# BatteryEmulator.net
KiCad netlist of a schematic drawn in Altium Designer
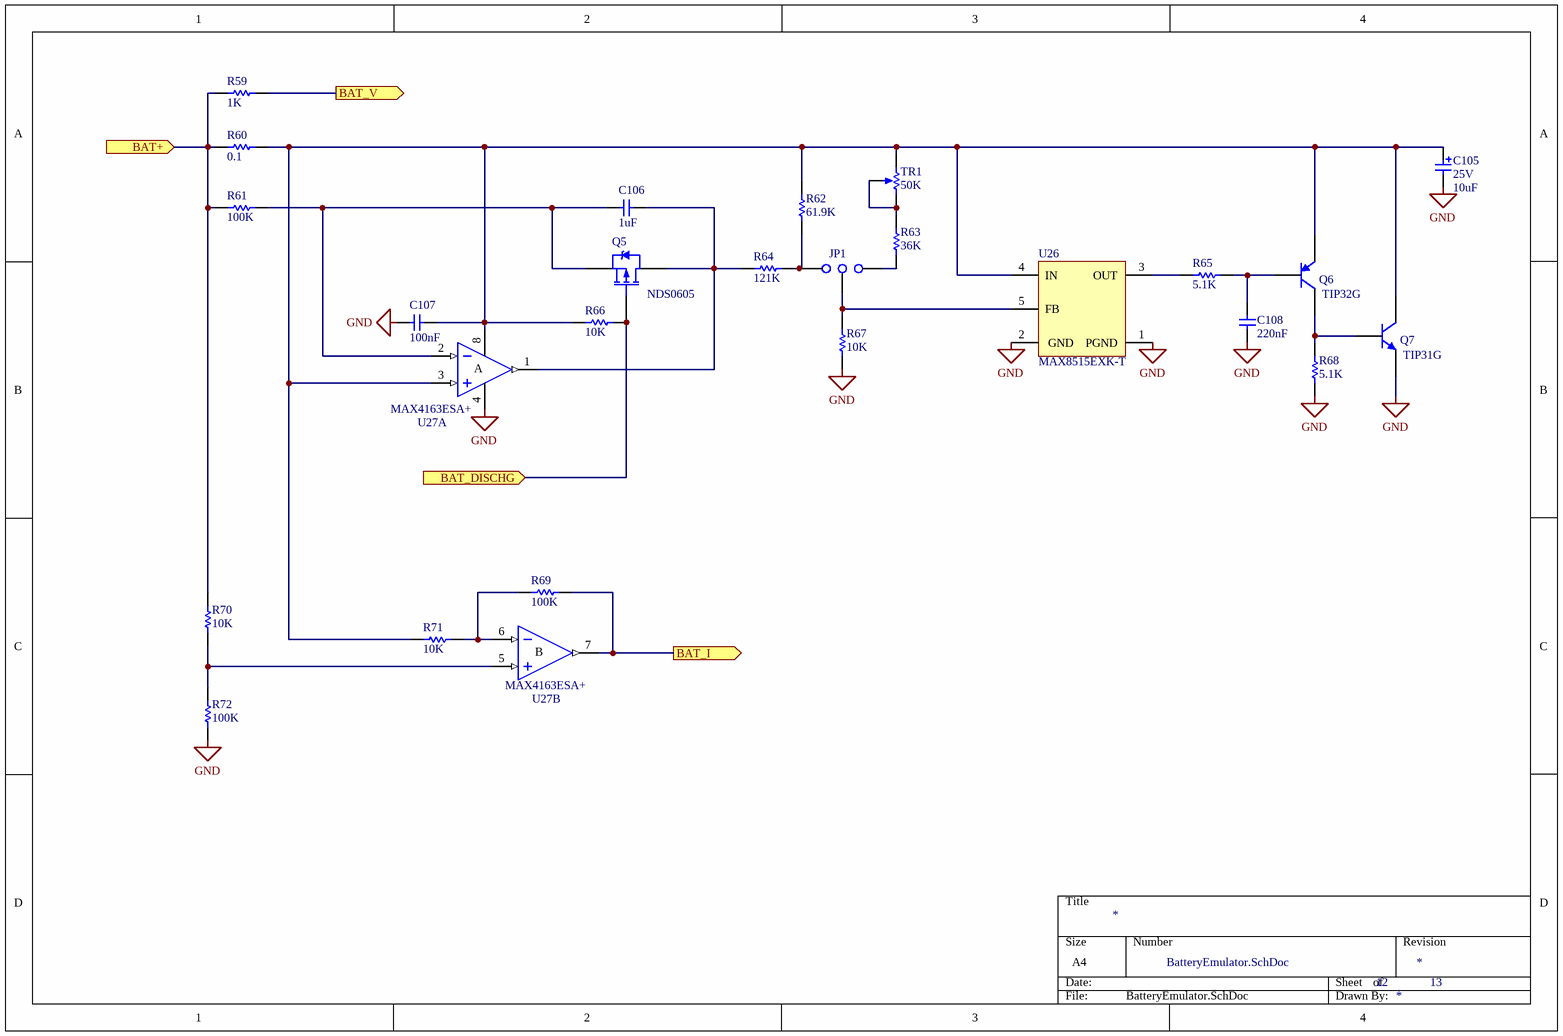
[diagram p0: BatteryEmulator.SchDoc]

(export (version "E")
  (design (tool "Eeschema 10.0.6"))
  (components
    (comp (ref "C105")
      (value "25V")
      (footprint "Cap Elet SMD 6.3 mm CASE D")
      (description "Condensatore elettrolitico")
      (fields (field (name "ALTIUM_VALUE") "10uF"))
      (libsource (lib "Plume") (part "Cap Elettrolitico"))
    )
    (comp (ref "C106")
      (value "1uF")
      (footprint "Cap Polyester 5 mm")
      (description "Polyester Capacitor")
      (fields (field (name "Comment") "Cap Polyester"))
      (libsource (lib "Plume") (part "Cap Polyester"))
    )
    (comp (ref "C107")
      (value "100nF")
      (footprint "0603M-C")
      (description "Ceramic Capacitor")
      (fields (field (name "Comment") "Cap Ceramic"))
      (libsource (lib "Plume") (part "Cap Ceramic"))
    )
    (comp (ref "C108")
      (value "220nF")
      (footprint "0603M-C")
      (description "Ceramic Capacitor")
      (fields (field (name "Comment") "Cap Ceramic"))
      (libsource (lib "Plume") (part "Cap Ceramic"))
    )
    (comp (ref "JP1") (value "Jumper 3 pin") (footprint "HEADER3") (libsource (lib "Plume") (part "Jumper3")))
    (comp (ref "Q5")
      (value "NDS0605")
      (footprint "SOT23 PMV65XP MOS")
      (description "Mosfet canale P Enhancement")
      (libsource (lib "Plume") (part "Transistor PMOS Enhancement"))
    )
    (comp (ref "Q6")
      (value "TIP32G")
      (footprint "TO220_BJT")
      (description "PNP Bipolar Transistor")
      (fields (field (name "PUBLISHER") "Altium Limited"))
      (libsource (lib "Plume") (part "Transistor PNP"))
    )
    (comp (ref "Q7")
      (value "TIP31G")
      (footprint "TO220_BJT")
      (description "NPN Bipolar Transistor")
      (libsource (lib "Plume") (part "Transistor NPN"))
    )
    (comp (ref "R59")
      (value "1K")
      (footprint "0603M")
      (description "Resistor")
      (libsource (lib "Plume") (part "Resistor"))
    )
    (comp (ref "R60")
      (value "0.1")
      (footprint "1206M")
      (description "Resistor")
      (libsource (lib "Plume") (part "Resistor"))
    )
    (comp (ref "R61")
      (value "100K")
      (footprint "0603M")
      (description "Resistor")
      (libsource (lib "Plume") (part "Resistor"))
    )
    (comp (ref "R62")
      (value "61.9K")
      (footprint "0603M")
      (description "Resistor")
      (libsource (lib "Plume") (part "Resistor"))
    )
    (comp (ref "R63")
      (value "36K")
      (footprint "0603M")
      (description "Resistor")
      (libsource (lib "Plume") (part "Resistor"))
    )
    (comp (ref "R64")
      (value "121K")
      (footprint "0603M")
      (description "Resistor")
      (libsource (lib "Plume") (part "Resistor"))
    )
    (comp (ref "R65")
      (value "5.1K")
      (footprint "0603M")
      (description "Resistor")
      (libsource (lib "Plume") (part "Resistor"))
    )
    (comp (ref "R66")
      (value "10K")
      (footprint "0603M")
      (description "Resistor")
      (libsource (lib "Plume") (part "Resistor"))
    )
    (comp (ref "R67")
      (value "10K")
      (footprint "0603M")
      (description "Resistor")
      (libsource (lib "Plume") (part "Resistor"))
    )
    (comp (ref "R68")
      (value "5.1K")
      (footprint "0603M")
      (description "Resistor")
      (libsource (lib "Plume") (part "Resistor"))
    )
    (comp (ref "R69")
      (value "100K")
      (footprint "0603M")
      (description "Resistor")
      (libsource (lib "Plume") (part "Resistor"))
    )
    (comp (ref "R70")
      (value "10K")
      (footprint "0603M")
      (description "Resistor")
      (libsource (lib "Plume") (part "Resistor"))
    )
    (comp (ref "R71")
      (value "10K")
      (footprint "0603M")
      (description "Resistor")
      (libsource (lib "Plume") (part "Resistor"))
    )
    (comp (ref "R72")
      (value "100K")
      (footprint "0603M")
      (description "Resistor")
      (libsource (lib "Plume") (part "Resistor"))
    )
    (comp (ref "TR1")
      (value "50K")
      (footprint "TRIMMER 3296W")
      (description "Trimmer")
      (fields (field (name "Comment") "Giri"))
      (libsource (lib "Plume") (part "Trimmer"))
    )
    (comp (ref "U26")
      (value "MAX8515EXK-T")
      (footprint "SC70-SOT65P210X110-5N")
      (description "Wide-Input 0.6V Shunt Regulators for Isolated DC-to-DC Converters")
      (libsource (lib "Plume") (part "MAX8515"))
    )
    (comp (ref "U27")
      (value "MAX4163ESA+")
      (footprint "SOIC127P600-8N")
      (description "Op Amps UCSP, Micropower, Single-Supply, 10V, Rail-to-Rail I/O")
      (libsource (lib "Plume") (part "MAX4163"))
    )
  )
  (nets
    (net (code "1") (name "/BAT+") (class "Default")
      (node (ref "R59") (pin "1") (pinfunction "1_1") (pintype "passive"))
      (node (ref "R60") (pin "1") (pinfunction "1_1") (pintype "passive"))
      (node (ref "R61") (pin "1") (pinfunction "1_1") (pintype "passive"))
      (node (ref "R70") (pin "2") (pinfunction "2_2") (pintype "passive"))
    )
    (net (code "2") (name "/BAT_DISCHG") (class "Default")
      (node (ref "Q5") (pin "1") (pinfunction "G_1") (pintype "passive"))
      (node (ref "R66") (pin "2") (pinfunction "2_2") (pintype "passive"))
    )
    (net (code "3") (name "/BAT_I") (class "Default")
      (node (ref "R69") (pin "2") (pinfunction "2_2") (pintype "passive"))
      (node (ref "U27") (pin "7") (pinfunction "OUT_7") (pintype "output"))
    )
    (net (code "4") (name "/BAT_V") (class "Default")
      (node (ref "R59") (pin "2") (pinfunction "2_2") (pintype "passive"))
    )
    (net (code "5") (name "GND") (class "Default")
      (node (ref "C105") (pin "2") (pinfunction "2_2") (pintype "passive"))
      (node (ref "C107") (pin "1") (pinfunction "1_1") (pintype "passive"))
      (node (ref "C108") (pin "1") (pinfunction "1_1") (pintype "passive"))
      (node (ref "Q7") (pin "3") (pinfunction "E_3") (pintype "passive"))
      (node (ref "R67") (pin "1") (pinfunction "1_1") (pintype "passive"))
      (node (ref "R68") (pin "2") (pinfunction "2_2") (pintype "passive"))
      (node (ref "R72") (pin "1") (pinfunction "1_1") (pintype "passive"))
      (node (ref "U26") (pin "1") (pinfunction "PGND_1") (pintype "passive"))
      (node (ref "U26") (pin "2") (pinfunction "_GND_2") (pintype "passive"))
      (node (ref "U27") (pin "4") (pinfunction "V-_4") (pintype "power_in"))
    )
    (net (code "6") (name "Net-(JP1-Pad1)") (class "Default")
      (node (ref "JP1") (pin "1") (pinfunction "1_1") (pintype "passive"))
      (node (ref "R62") (pin "1") (pinfunction "1_1") (pintype "passive"))
      (node (ref "R64") (pin "2") (pinfunction "2_2") (pintype "passive"))
    )
    (net (code "7") (name "Net-(JP1-Pad3)") (class "Default")
      (node (ref "JP1") (pin "3") (pinfunction "3_3") (pintype "passive"))
      (node (ref "R63") (pin "1") (pinfunction "1_1") (pintype "passive"))
    )
    (net (code "8") (name "Net-(Q5-D)") (class "Default")
      (node (ref "C106") (pin "2") (pinfunction "2_2") (pintype "passive"))
      (node (ref "Q5") (pin "2") (pinfunction "D_2") (pintype "passive"))
      (node (ref "R64") (pin "1") (pinfunction "1_1") (pintype "passive"))
      (node (ref "U27") (pin "1") (pinfunction "OUT_1") (pintype "output"))
    )
    (net (code "9") (name "Net-(Q5-S)") (class "Default")
      (node (ref "C106") (pin "1") (pinfunction "1_1") (pintype "passive"))
      (node (ref "Q5") (pin "3") (pinfunction "S_3") (pintype "passive"))
      (node (ref "R61") (pin "2") (pinfunction "2_2") (pintype "passive"))
      (node (ref "U27") (pin "2") (pinfunction "IN-_2") (pintype "input"))
    )
    (net (code "10") (name "Net-(Q6-B)") (class "Default")
      (node (ref "C108") (pin "2") (pinfunction "2_2") (pintype "passive"))
      (node (ref "Q6") (pin "2") (pinfunction "B_2") (pintype "passive"))
      (node (ref "R65") (pin "1") (pinfunction "1_1") (pintype "passive"))
    )
    (net (code "11") (name "Net-(Q6-C)") (class "Default")
      (node (ref "Q6") (pin "1") (pinfunction "C_1") (pintype "passive"))
      (node (ref "Q7") (pin "2") (pinfunction "B_2") (pintype "passive"))
      (node (ref "R68") (pin "1") (pinfunction "1_1") (pintype "passive"))
    )
    (net (code "12") (name "Net-(Q6-E)") (class "Default")
      (node (ref "C105") (pin "1") (pinfunction "1_1") (pintype "passive"))
      (node (ref "C107") (pin "2") (pinfunction "2_2") (pintype "passive"))
      (node (ref "Q6") (pin "3") (pinfunction "E_3") (pintype "passive"))
      (node (ref "Q7") (pin "1") (pinfunction "C_1") (pintype "passive"))
      (node (ref "R60") (pin "2") (pinfunction "2_2") (pintype "passive"))
      (node (ref "R62") (pin "2") (pinfunction "2_2") (pintype "passive"))
      (node (ref "R66") (pin "1") (pinfunction "1_1") (pintype "passive"))
      (node (ref "R71") (pin "1") (pinfunction "1_1") (pintype "passive"))
      (node (ref "TR1") (pin "1") (pinfunction "TOP_1") (pintype "passive"))
      (node (ref "U26") (pin "4") (pinfunction "IN_4") (pintype "passive"))
      (node (ref "U27") (pin "3") (pinfunction "IN+_3") (pintype "input"))
      (node (ref "U27") (pin "8") (pinfunction "V+_8") (pintype "power_in"))
    )
    (net (code "13") (name "Net-(TR1-BOT)") (class "Default")
      (node (ref "R63") (pin "2") (pinfunction "2_2") (pintype "passive"))
      (node (ref "TR1") (pin "2") (pinfunction "BOT_2") (pintype "passive"))
      (node (ref "TR1") (pin "3") (pinfunction "TAP_3") (pintype "passive"))
    )
    (net (code "14") (name "Net-(U26-FB)") (class "Default")
      (node (ref "JP1") (pin "2") (pinfunction "2_2") (pintype "passive"))
      (node (ref "R67") (pin "2") (pinfunction "2_2") (pintype "passive"))
      (node (ref "U26") (pin "5") (pinfunction "FB_5") (pintype "passive"))
    )
    (net (code "15") (name "Net-(U26-OUT)") (class "Default")
      (node (ref "R65") (pin "2") (pinfunction "2_2") (pintype "passive"))
      (node (ref "U26") (pin "3") (pinfunction "OUT_3") (pintype "passive"))
    )
    (net (code "16") (name "Net-(U27B-IN+)") (class "Default")
      (node (ref "R70") (pin "1") (pinfunction "1_1") (pintype "passive"))
      (node (ref "R72") (pin "2") (pinfunction "2_2") (pintype "passive"))
      (node (ref "U27") (pin "5") (pinfunction "IN+_5") (pintype "input"))
    )
    (net (code "17") (name "Net-(U27B-IN-)") (class "Default")
      (node (ref "R69") (pin "1") (pinfunction "1_1") (pintype "passive"))
      (node (ref "R71") (pin "2") (pinfunction "2_2") (pintype "passive"))
      (node (ref "U27") (pin "6") (pinfunction "IN-_6") (pintype "input"))
    )
  )
)
